# Port.net
KiCad netlist of a schematic drawn in Altium Designer
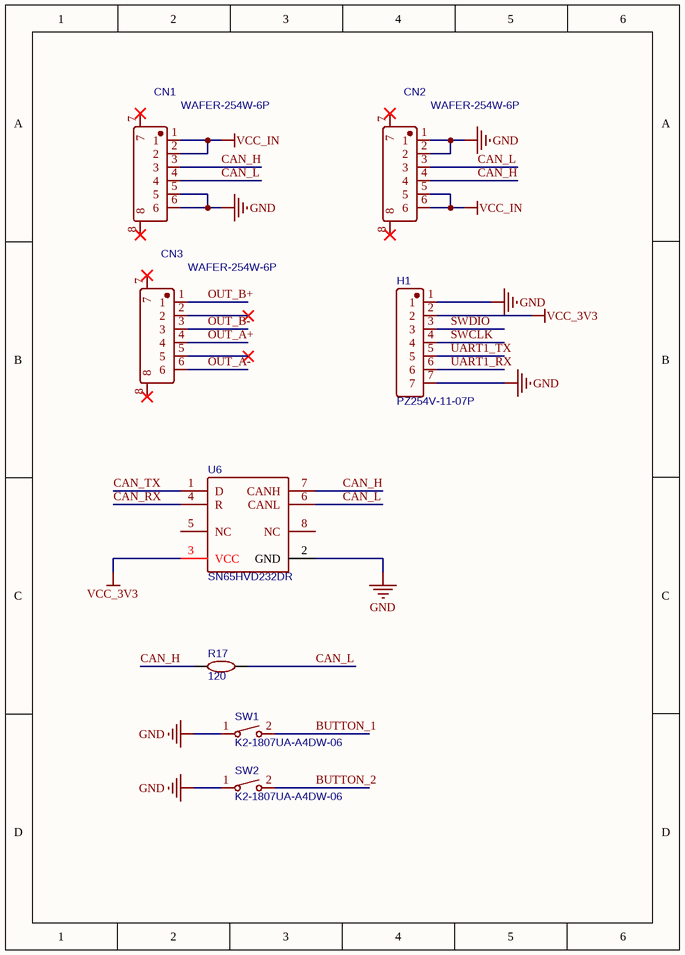
[diagram p0: Port.SchDoc]

(export (version "E")
  (design (tool "Eeschema 10.0.6"))
  (components
    (comp (ref "CN1")
      (value "WAFER-254W-6P")
      (footprint "CONN-SMD_WAFER-254W-6P")
      (fields (field (name "BOM_SUPPLIER PART") "C2856747") (field (name "CONTRIBUTOR") "LCSC"))
      (libsource (lib "6P 2.54mm") (part "WAFER-254W-6P"))
    )
    (comp (ref "CN2")
      (value "WAFER-254W-6P")
      (footprint "CONN-SMD_WAFER-254W-6P")
      (fields (field (name "BOM_SUPPLIER PART") "C2856747") (field (name "CONTRIBUTOR") "LCSC"))
      (libsource (lib "6P 2.54mm") (part "WAFER-254W-6P"))
    )
    (comp (ref "CN3")
      (value "WAFER-254W-6P")
      (footprint "CONN-SMD_WAFER-254W-6P")
      (fields (field (name "BOM_SUPPLIER PART") "C2856747") (field (name "CONTRIBUTOR") "LCSC"))
      (libsource (lib "6P 2.54mm") (part "WAFER-254W-6P"))
    )
    (comp (ref "H1")
      (value "PZ254V-11-07P")
      (footprint "HDR-TH_7P-P2.54-V-M")
      (fields (field (name "BOM_SUPPLIER PART") "C492406") (field (name "CONTRIBUTOR") "LCSC"))
      (libsource (lib "7P 2.54mm") (part "PZ254V-11-07P"))
    )
    (comp (ref "R17")
      (value "120")
      (footprint "R0603")
      (fields
        (field (name "BOM_MANUFACTURER PART") "0603WAF1200T5E")
        (field (name "BOM_SUPPLIER PART") "C22787")
      )
      (libsource (lib "120R") (part "120"))
    )
    (comp (ref "SW1")
      (value "K2-1807UA-A4DW-06")
      (footprint "KEY-SMD_L4.0-W2.9-L")
      (fields (field (name "BOM_SUPPLIER PART") "C502307") (field (name "CONTRIBUTOR") "LCSC"))
      (libsource (lib "BUTTON") (part "K2-1807UA-A4DW-06"))
    )
    (comp (ref "SW2")
      (value "K2-1807UA-A4DW-06")
      (footprint "KEY-SMD_L4.0-W2.9-L")
      (fields (field (name "BOM_SUPPLIER PART") "C502307") (field (name "CONTRIBUTOR") "LCSC"))
      (libsource (lib "BUTTON") (part "K2-1807UA-A4DW-06"))
    )
    (comp (ref "U6")
      (value "SN65HVD232DR")
      (footprint "SOIC-8_L5.0-W4.0-P1.27-LS6.0-BL")
      (fields (field (name "BOM_SUPPLIER PART") "C30530"))
      (libsource (lib "SN65HVD232DR") (part "SN65HVD232DR"))
    )
  )
  (nets
    (net (code "1") (name "/BUTTON_1") (class "Default")
      (node (ref "SW1") (pin "2") (pinfunction "2_2") (pintype "passive"))
    )
    (net (code "2") (name "/BUTTON_2") (class "Default")
      (node (ref "SW2") (pin "2") (pinfunction "2_2") (pintype "passive"))
    )
    (net (code "3") (name "/CAN_H") (class "Default")
      (node (ref "CN1") (pin "3") (pinfunction "3_3") (pintype "passive"))
      (node (ref "CN2") (pin "4") (pinfunction "4_4") (pintype "passive"))
      (node (ref "R17") (pin "1") (pinfunction "1_1") (pintype "passive"))
      (node (ref "U6") (pin "7") (pinfunction "CANH_7") (pintype "passive"))
    )
    (net (code "4") (name "/CAN_L") (class "Default")
      (node (ref "CN1") (pin "4") (pinfunction "4_4") (pintype "passive"))
      (node (ref "CN2") (pin "3") (pinfunction "3_3") (pintype "passive"))
      (node (ref "R17") (pin "2") (pinfunction "2_2") (pintype "passive"))
      (node (ref "U6") (pin "6") (pinfunction "CANL_6") (pintype "passive"))
    )
    (net (code "5") (name "/CAN_RX") (class "Default")
      (node (ref "U6") (pin "4") (pinfunction "R_4") (pintype "passive"))
    )
    (net (code "6") (name "/CAN_TX") (class "Default")
      (node (ref "U6") (pin "1") (pinfunction "D_1") (pintype "passive"))
    )
    (net (code "7") (name "/OUT_A+") (class "Default")
      (node (ref "CN3") (pin "4") (pinfunction "4_4") (pintype "passive"))
    )
    (net (code "8") (name "/OUT_A-") (class "Default")
      (node (ref "CN3") (pin "6") (pinfunction "6_6") (pintype "passive"))
    )
    (net (code "9") (name "/OUT_B+") (class "Default")
      (node (ref "CN3") (pin "1") (pinfunction "1_1") (pintype "passive"))
    )
    (net (code "10") (name "/OUT_B-") (class "Default")
      (node (ref "CN3") (pin "3") (pinfunction "3_3") (pintype "passive"))
    )
    (net (code "11") (name "/SWCLK") (class "Default")
      (node (ref "H1") (pin "4") (pinfunction "4_4") (pintype "passive"))
    )
    (net (code "12") (name "/SWDIO") (class "Default")
      (node (ref "H1") (pin "3") (pinfunction "3_3") (pintype "passive"))
    )
    (net (code "13") (name "/UART1_RX") (class "Default")
      (node (ref "H1") (pin "6") (pinfunction "6_6") (pintype "passive"))
    )
    (net (code "14") (name "/UART1_TX") (class "Default")
      (node (ref "H1") (pin "5") (pinfunction "5_5") (pintype "passive"))
    )
    (net (code "15") (name "GND") (class "Default")
      (node (ref "CN1") (pin "5") (pinfunction "5_5") (pintype "passive"))
      (node (ref "CN1") (pin "6") (pinfunction "6_6") (pintype "passive"))
      (node (ref "CN2") (pin "1") (pinfunction "1_1") (pintype "passive"))
      (node (ref "CN2") (pin "2") (pinfunction "2_2") (pintype "passive"))
      (node (ref "H1") (pin "1") (pinfunction "1_1") (pintype "passive"))
      (node (ref "H1") (pin "7") (pinfunction "7_7") (pintype "passive"))
      (node (ref "SW1") (pin "1") (pinfunction "1_1") (pintype "passive"))
      (node (ref "SW2") (pin "1") (pinfunction "1_1") (pintype "passive"))
      (node (ref "U6") (pin "2") (pinfunction "GND_2") (pintype "passive"))
    )
    (net (code "16") (name "VCC_3V3") (class "Default")
      (node (ref "H1") (pin "2") (pinfunction "2_2") (pintype "passive"))
      (node (ref "U6") (pin "3") (pinfunction "VCC_3") (pintype "passive"))
    )
    (net (code "17") (name "VCC_IN") (class "Default")
      (node (ref "CN1") (pin "1") (pinfunction "1_1") (pintype "passive"))
      (node (ref "CN1") (pin "2") (pinfunction "2_2") (pintype "passive"))
      (node (ref "CN2") (pin "5") (pinfunction "5_5") (pintype "passive"))
      (node (ref "CN2") (pin "6") (pinfunction "6_6") (pintype "passive"))
    )
    (net (code "18") (name "unconnected-(CN1-Pad7)") (class "Default")
      (node (ref "CN1") (pin "7") (pinfunction "7_7") (pintype "passive+no_connect"))
    )
    (net (code "19") (name "unconnected-(CN1-Pad8)") (class "Default")
      (node (ref "CN1") (pin "8") (pinfunction "8_8") (pintype "passive+no_connect"))
    )
    (net (code "20") (name "unconnected-(CN2-Pad7)") (class "Default")
      (node (ref "CN2") (pin "7") (pinfunction "7_7") (pintype "passive+no_connect"))
    )
    (net (code "21") (name "unconnected-(CN2-Pad8)") (class "Default")
      (node (ref "CN2") (pin "8") (pinfunction "8_8") (pintype "passive+no_connect"))
    )
    (net (code "22") (name "unconnected-(CN3-Pad2)") (class "Default")
      (node (ref "CN3") (pin "2") (pinfunction "2_2") (pintype "passive+no_connect"))
    )
    (net (code "23") (name "unconnected-(CN3-Pad5)") (class "Default")
      (node (ref "CN3") (pin "5") (pinfunction "5_5") (pintype "passive+no_connect"))
    )
    (net (code "24") (name "unconnected-(CN3-Pad7)") (class "Default")
      (node (ref "CN3") (pin "7") (pinfunction "7_7") (pintype "passive+no_connect"))
    )
    (net (code "25") (name "unconnected-(CN3-Pad8)") (class "Default")
      (node (ref "CN3") (pin "8") (pinfunction "8_8") (pintype "passive+no_connect"))
    )
    (net (code "26") (name "unconnected-(U6-NC-Pad5)") (class "Default")
      (node (ref "U6") (pin "5") (pinfunction "NC_5") (pintype "passive"))
    )
    (net (code "27") (name "unconnected-(U6-NC-Pad8)") (class "Default")
      (node (ref "U6") (pin "8") (pinfunction "NC_8") (pintype "passive"))
    )
  )
)
